# 48-17V_Buck_Converter.net
KiCad netlist of a schematic drawn in Altium Designer
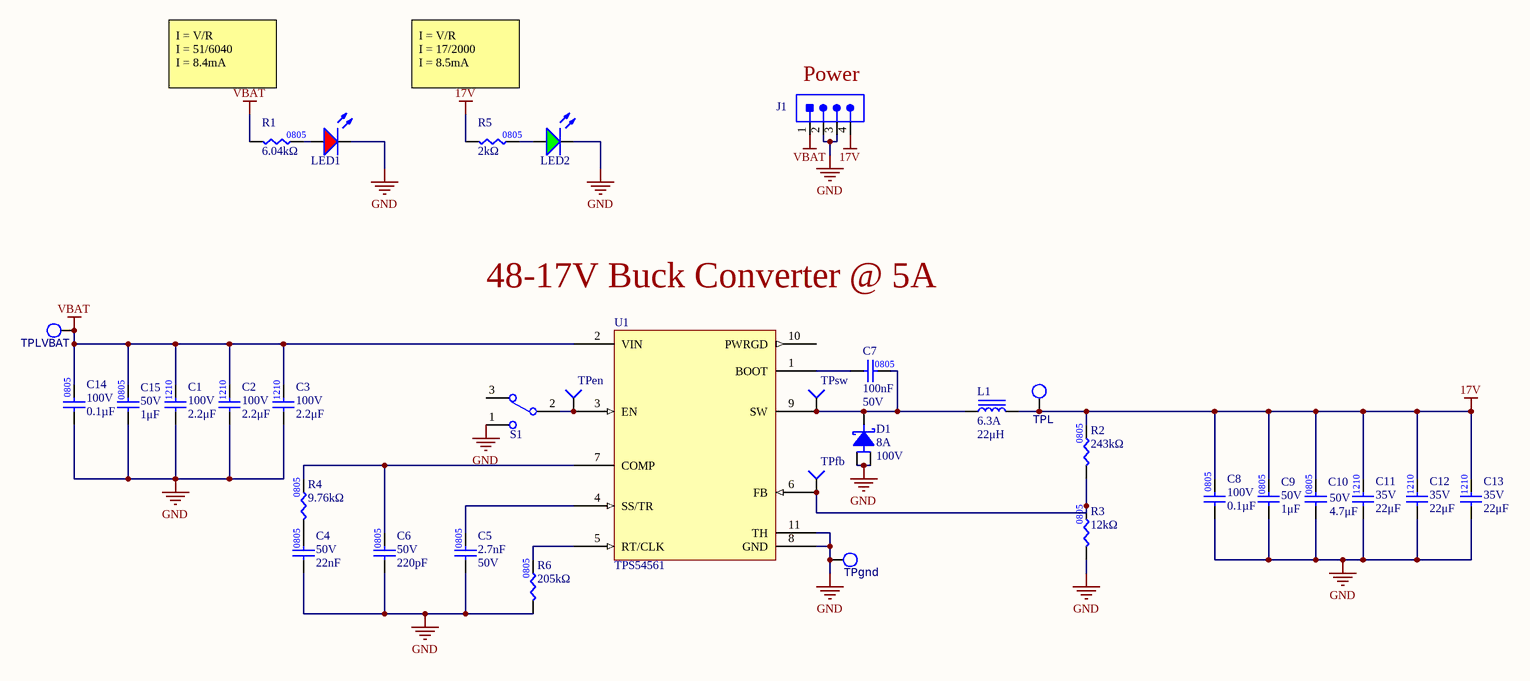
[diagram p0: 48-17V Buck Converter.SchDoc]

(export (version "E")
  (design (tool "Eeschema 10.0.6"))
  (components
    (comp (ref "C1")
      (value "2.2μF")
      (footprint "CAPC3225X270N")
      (description "CAP CER 2.2UF 100V X7R 1210")
      (fields (field (name "VOLTAGE RATING") "100V") (field (name "Comment") "CAP_2.2uF_100V_1210_1"))
      (libsource (lib "UWRT_Schematic_Library_2020") (part "CAP_2.2uF_100V_1210_1"))
    )
    (comp (ref "C2")
      (value "2.2μF")
      (footprint "CAPC3225X270N")
      (description "CAP CER 2.2UF 100V X7R 1210")
      (fields (field (name "VOLTAGE RATING") "100V") (field (name "Comment") "CAP_2.2uF_100V_1210_1"))
      (libsource (lib "UWRT_Schematic_Library_2020") (part "CAP_2.2uF_100V_1210_1"))
    )
    (comp (ref "C3")
      (value "2.2μF")
      (footprint "CAPC3225X270N")
      (description "CAP CER 2.2UF 100V X7R 1210")
      (fields (field (name "VOLTAGE RATING") "100V") (field (name "Comment") "CAP_2.2uF_100V_1210_1"))
      (libsource (lib "UWRT_Schematic_Library_2020") (part "CAP_2.2uF_100V_1210_1"))
    )
    (comp (ref "C4")
      (value "22nF")
      (footprint "CAP2012")
      (description "CAP CER 22nF 50V 0805")
      (fields (field (name "VOLTAGE RATING") "50V") (field (name "Comment") "CAP_22nF_50V_0805 +/- 1%"))
      (libsource (lib "UWRT_Schematic_Library_2020") (part "CAP_22nF_50V_0805 +/- 1%"))
    )
    (comp (ref "C5")
      (value "2.7nF")
      (footprint "CAP0805")
      (description "CAP CER 2700PF 50V C0G 0805")
      (fields (field (name "VOLTAGE RATING") "50V") (field (name "Comment") "CAP_2.7nF_50V_0805"))
      (libsource (lib "UWRT_Schematic_Library_2020") (part "CAP_2.7nF_50V_0805"))
    )
    (comp (ref "C6")
      (value "220pF")
      (footprint "CAP2012")
      (description "CAP CER 220pF 50V 0805 +/-1%")
      (fields (field (name "VOLTAGE RATING") "50V") (field (name "Comment") "CAP_220pF_50V_0805_2_1"))
      (libsource (lib "UWRT_Schematic_Library_2020") (part "CAP_220pF_50V_0805_2_1"))
    )
    (comp (ref "C7")
      (value "100nF")
      (footprint "CAP0805")
      (description "CAP CER 0.1UF 50V X7R 0805")
      (fields (field (name "VOLTAGE RATING") "50V") (field (name "Comment") "CAP_100nF_50V_0805"))
      (libsource (lib "UWRT_Schematic_Library_2020") (part "CAP_100nF_50V_0805"))
    )
    (comp (ref "C8")
      (value "0.1µF")
      (footprint "CAP0805")
      (description "CAP CER 0.1UF 100V X7R 0805")
      (fields (field (name "VOLTAGE RATING") "100V") (field (name "Comment") "CAP_0.1uF_100V_0805"))
      (libsource (lib "UWRT_Schematic_Library_2020") (part "CAP_0.1uF_100V_0805"))
    )
    (comp (ref "C9")
      (value "1μF")
      (footprint "CAP2012")
      (description "CAP CER 1UF 50V X7R 0805")
      (fields
        (field (name "LCSC PART #") "C28323")
        (field (name "VOLTAGE RATING") "50V")
        (field (name "Comment") "CAP_1uF_50V_0805")
      )
      (libsource (lib "UWRT_Schematic_Library_2020") (part "CAP_1uF_50V_0805"))
    )
    (comp (ref "C10")
      (value "4.7μF")
      (footprint "CAP0805")
      (description "CAP CER 4.7UF 50V X5R 0805")
      (fields
        (field (name "LCSC PART #") "C1779")
        (field (name "VOLTAGE RATING") "50V")
        (field (name "Comment") "CAP_4.7uF_50V_0805")
      )
      (libsource (lib "UWRT_Schematic_Library_2020") (part "CAP_4.7uF_50V_0805"))
    )
    (comp (ref "C11")
      (value "22μF")
      (footprint "CAP1210")
      (description "CAP CER 22UF 35V X5R 1210")
      (fields (field (name "VOLTAGE RATING") "35V") (field (name "Comment") "CAP_22uF_100V_1210"))
      (libsource (lib "UWRT_Schematic_Library_2020") (part "CAP_22uF_100V_1210"))
    )
    (comp (ref "C12")
      (value "22μF")
      (footprint "CAP1210")
      (description "CAP CER 22UF 35V X5R 1210")
      (fields (field (name "VOLTAGE RATING") "35V") (field (name "Comment") "CAP_22uF_100V_1210"))
      (libsource (lib "UWRT_Schematic_Library_2020") (part "CAP_22uF_100V_1210"))
    )
    (comp (ref "C13")
      (value "22μF")
      (footprint "CAP1210")
      (description "CAP CER 22UF 35V X5R 1210")
      (fields (field (name "VOLTAGE RATING") "35V") (field (name "Comment") "CAP_22uF_100V_1210"))
      (libsource (lib "UWRT_Schematic_Library_2020") (part "CAP_22uF_100V_1210"))
    )
    (comp (ref "C14")
      (value "0.1µF")
      (footprint "CAP0805")
      (description "CAP CER 0.1UF 100V X7R 0805")
      (fields (field (name "VOLTAGE RATING") "100V") (field (name "Comment") "CAP_0.1uF_100V_0805"))
      (libsource (lib "UWRT_Schematic_Library_2020") (part "CAP_0.1uF_100V_0805"))
    )
    (comp (ref "C15")
      (value "1μF")
      (footprint "CAP2012")
      (description "CAP CER 1UF 50V X7R 0805")
      (fields
        (field (name "LCSC PART #") "C28323")
        (field (name "VOLTAGE RATING") "50V")
        (field (name "Comment") "CAP_1uF_50V_0805")
      )
      (libsource (lib "UWRT_Schematic_Library_2020") (part "CAP_1uF_50V_0805"))
    )
    (comp (ref "D1")
      (value "8A")
      (footprint "TO-277")
      (description "Diode 100 V 8A Surface Mount TO-277")
      (fields (field (name "VR (MAX)") "100V"))
      (libsource (lib "UWRT_Schematic_Library_2020") (part "DIO_SCHOTTKY_100V_8A"))
    )
    (comp (ref "J1")
      (value "CON_2POS_SCREW_TERM")
      (footprint "MPT-04-01-01-L-RA-SD")
      (description "CONN HDR 4POS 5MM R/A SLDR")
      (libsource (lib "UWRT_Schematic_Library_2020") (part "CON_4POS_POWERBLADE_MALE"))
    )
    (comp (ref "L1")
      (value "IND_22uH_6.3A")
      (footprint "UWRT_Footprint_Library_2020:IND_22uH_6.3A")
      (description "FIXED IND 22UH 6.3A 25.7MOHM SMD")
      (fields (field (name "CURRENT RATING") "6.3A") (field (name "INDUCTANCE") "22μH"))
      (libsource (lib "UWRT_Schematic_Library_2020") (part "IND_22uH_6.3A"))
    )
    (comp (ref "LED1")
      (value "LED_RED")
      (footprint "LED_0805_RED")
      (description "LED RED DIFFUSED 0805 SMD")
      (libsource (lib "UWRT_Schematic_Library_2020") (part "LED_RED"))
    )
    (comp (ref "LED2")
      (value "LED_GREEN")
      (footprint "LED_0805_GREEN")
      (description "LED GREEN DIFFUSED 0805 SMD")
      (libsource (lib "UWRT_Schematic_Library_2020") (part "LED_GREEN"))
    )
    (comp (ref "R1")
      (value "6.04kΩ")
      (footprint "RES0805")
      (description "RES 6.04K OHM 1% 1/8W 0805")
      (fields (field (name "Comment") "RES_6.04kΩ_0805_1%"))
      (libsource (lib "UWRT_Schematic_Library_2020") (part "RES_6.04kΩ_0805_1%"))
    )
    (comp (ref "R2")
      (value "243kΩ")
      (footprint "RES0805")
      (description "RES 243K OHM 1% 1/8W 0805")
      (fields (field (name "Comment") "RES_243kΩ_0805_1%_1"))
      (libsource (lib "UWRT_Schematic_Library_2020") (part "RES_243kΩ_0805_1%_1"))
    )
    (comp (ref "R3")
      (value "12kΩ")
      (footprint "RES0805")
      (description "RES 12K OHM 1% 1/8W 0805")
      (fields (field (name "Comment") "RES_12kΩ_0805_1%"))
      (libsource (lib "UWRT_Schematic_Library_2020") (part "RES_12kΩ_0805_1%"))
    )
    (comp (ref "R4")
      (value "9.76kΩ")
      (footprint "RES0805")
      (description "RES 9.76K OHM 1% 1/8W 0805")
      (fields (field (name "Comment") "RES_9.76kΩ_0805_1%"))
      (libsource (lib "UWRT_Schematic_Library_2020") (part "RES_9.76kΩ_0805_1%"))
    )
    (comp (ref "R5")
      (value "2kΩ")
      (footprint "RES0805")
      (description "RES 2K OHM 1% 1/8W 0805")
      (fields (field (name "TOLERANCE") "1%") (field (name "Comment") "RES_2KΩ_0805_1%"))
      (libsource (lib "UWRT_Schematic_Library_2020") (part "RES_2KΩ_0805_1%"))
    )
    (comp (ref "R6")
      (value "205kΩ")
      (footprint "RES0805")
      (description "RES 205K OHM 1% 1/8W 0805")
      (fields (field (name "Comment") "RES_205kΩ_0805_1%"))
      (libsource (lib "UWRT_Schematic_Library_2020") (part "RES_205kΩ_0805_1%"))
    )
    (comp (ref "S1")
      (value "SW_SLIDE_TOGGLE")
      (footprint "UWRT_Footprint_Library_2020:SW_SLIDE_TOGGLE")
      (description "SWITCH SLIDE SPDT 200MA 30V")
      (libsource (lib "UWRT_Schematic_Library_2020") (part "SW_SLIDE_TOGGLE"))
    )
    (comp (ref "TPen")
      (value "TESTPOINT_1MM_CIRCLE")
      (footprint "TESTPOINT_CIRCLE_1MM")
      (description "TESTPOINT 1MM CIRCLE")
      (libsource (lib "UWRT_Schematic_Library_2020") (part "TESTPOINT_1MM_CIRCLE"))
    )
    (comp (ref "TPfb")
      (value "TESTPOINT_1MM_CIRCLE")
      (footprint "TESTPOINT_CIRCLE_1MM")
      (description "TESTPOINT 1MM CIRCLE")
      (libsource (lib "UWRT_Schematic_Library_2020") (part "TESTPOINT_1MM_CIRCLE"))
    )
    (comp (ref "TPgnd")
      (value "TESTPOINT_LOOP")
      (footprint "TESTPOINT_LOOP")
      (description "TESTPOINT THRUHOLE")
      (libsource (lib "UWRT_Schematic_Library_2020") (part "TESTPOINT_LOOP"))
    )
    (comp (ref "TPL")
      (value "TESTPOINT_LOOP")
      (footprint "TESTPOINT_LOOP")
      (description "TESTPOINT THRUHOLE")
      (libsource (lib "UWRT_Schematic_Library_2020") (part "TESTPOINT_LOOP"))
    )
    (comp (ref "TPLVBAT")
      (value "TESTPOINT_LOOP")
      (footprint "TESTPOINT_LOOP")
      (description "TESTPOINT THRUHOLE")
      (libsource (lib "UWRT_Schematic_Library_2020") (part "TESTPOINT_LOOP"))
    )
    (comp (ref "TPsw")
      (value "TESTPOINT_1MM_CIRCLE")
      (footprint "TESTPOINT_CIRCLE_1MM")
      (description "TESTPOINT 1MM CIRCLE")
      (libsource (lib "UWRT_Schematic_Library_2020") (part "TESTPOINT_1MM_CIRCLE"))
    )
    (comp (ref "U1")
      (value "TPS54561")
      (footprint "BUCK_TPS54561DPRR")
      (description "Buck Switching Regulator IC Positive Adjustable 0.8V 1 Output 5A 10-WDFN Exposed Pad")
      (libsource (lib "UWRT_Schematic_Library_2020") (part "TPS54561"))
    )
  )
  (nets
    (net (code "1") (name "17V") (class "Default")
      (node (ref "C10") (pin "2") (pinfunction "2_2") (pintype "passive"))
      (node (ref "C11") (pin "2") (pinfunction "2_2") (pintype "passive"))
      (node (ref "C12") (pin "2") (pinfunction "2_2") (pintype "passive"))
      (node (ref "C13") (pin "2") (pinfunction "2_2") (pintype "passive"))
      (node (ref "C8") (pin "2") (pinfunction "2_2") (pintype "passive"))
      (node (ref "C9") (pin "2") (pinfunction "2_2") (pintype "passive"))
      (node (ref "J1") (pin "4") (pinfunction "2_4") (pintype "passive"))
      (node (ref "L1") (pin "2") (pinfunction "2_2") (pintype "passive"))
      (node (ref "R2") (pin "2") (pinfunction "2_2") (pintype "passive"))
      (node (ref "R5") (pin "1") (pinfunction "1_1") (pintype "passive"))
      (node (ref "TPL") (pin "1") (pintype "passive"))
    )
    (net (code "2") (name "GND") (class "Default")
      (node (ref "C1") (pin "1") (pinfunction "1_1") (pintype "passive"))
      (node (ref "C10") (pin "1") (pinfunction "1_1") (pintype "passive"))
      (node (ref "C11") (pin "1") (pinfunction "1_1") (pintype "passive"))
      (node (ref "C12") (pin "1") (pinfunction "1_1") (pintype "passive"))
      (node (ref "C13") (pin "1") (pinfunction "1_1") (pintype "passive"))
      (node (ref "C14") (pin "1") (pinfunction "1_1") (pintype "passive"))
      (node (ref "C15") (pin "1") (pinfunction "1_1") (pintype "passive"))
      (node (ref "C2") (pin "1") (pinfunction "1_1") (pintype "passive"))
      (node (ref "C3") (pin "1") (pinfunction "1_1") (pintype "passive"))
      (node (ref "C4") (pin "1") (pinfunction "1_1") (pintype "passive"))
      (node (ref "C5") (pin "1") (pinfunction "1_1") (pintype "passive"))
      (node (ref "C6") (pin "1") (pinfunction "1_1") (pintype "passive"))
      (node (ref "C8") (pin "1") (pinfunction "1_1") (pintype "passive"))
      (node (ref "C9") (pin "1") (pinfunction "1_1") (pintype "passive"))
      (node (ref "D1") (pin "1") (pinfunction "Anode_1") (pintype "passive"))
      (node (ref "D1") (pin "3") (pintype "passive"))
      (node (ref "J1") (pin "2") (pinfunction "2_2") (pintype "passive"))
      (node (ref "J1") (pin "3") (pinfunction "1_3") (pintype "passive"))
      (node (ref "LED1") (pin "2") (pinfunction "K_2") (pintype "passive"))
      (node (ref "LED2") (pin "2") (pinfunction "K_2") (pintype "passive"))
      (node (ref "R3") (pin "1") (pinfunction "1_1") (pintype "passive"))
      (node (ref "R6") (pin "1") (pinfunction "1_1") (pintype "passive"))
      (node (ref "S1") (pin "1") (pinfunction "1_1") (pintype "passive"))
      (node (ref "TPgnd") (pin "1") (pintype "passive"))
      (node (ref "U1") (pin "11") (pinfunction "TH_11") (pintype "power_in"))
      (node (ref "U1") (pin "8") (pinfunction "GND_8") (pintype "power_in"))
    )
    (net (code "3") (name "Net-(C4-Pad2)") (class "Default")
      (node (ref "C4") (pin "2") (pinfunction "2_2") (pintype "passive"))
      (node (ref "R4") (pin "1") (pinfunction "1_1") (pintype "passive"))
    )
    (net (code "4") (name "Net-(D1-Cathode)") (class "Default")
      (node (ref "C7") (pin "2") (pinfunction "2_2") (pintype "passive"))
      (node (ref "D1") (pin "2") (pinfunction "Cathode_2") (pintype "passive"))
      (node (ref "L1") (pin "1") (pinfunction "1_1") (pintype "passive"))
      (node (ref "TPsw") (pin "1") (pinfunction "=value_1") (pintype "passive"))
      (node (ref "U1") (pin "9") (pinfunction "SW_9") (pintype "power_in"))
    )
    (net (code "5") (name "Net-(LED1-A)") (class "Default")
      (node (ref "LED1") (pin "1") (pinfunction "A_1") (pintype "passive"))
      (node (ref "R1") (pin "2") (pinfunction "2_2") (pintype "passive"))
    )
    (net (code "6") (name "Net-(LED2-A)") (class "Default")
      (node (ref "LED2") (pin "1") (pinfunction "A_1") (pintype "passive"))
      (node (ref "R5") (pin "2") (pinfunction "2_2") (pintype "passive"))
    )
    (net (code "7") (name "Net-(TPen-=value)") (class "Default")
      (node (ref "S1") (pin "2") (pinfunction "2_2") (pintype "passive"))
      (node (ref "TPen") (pin "1") (pinfunction "=value_1") (pintype "passive"))
      (node (ref "U1") (pin "3") (pinfunction "EN_3") (pintype "input"))
    )
    (net (code "8") (name "Net-(TPfb-=value)") (class "Default")
      (node (ref "R2") (pin "1") (pinfunction "1_1") (pintype "passive"))
      (node (ref "R3") (pin "2") (pinfunction "2_2") (pintype "passive"))
      (node (ref "TPfb") (pin "1") (pinfunction "=value_1") (pintype "passive"))
      (node (ref "U1") (pin "6") (pinfunction "FB_6") (pintype "input"))
    )
    (net (code "9") (name "Net-(U1-BOOT)") (class "Default")
      (node (ref "C7") (pin "1") (pinfunction "1_1") (pintype "passive"))
      (node (ref "U1") (pin "1") (pinfunction "BOOT_1") (pintype "power_in"))
    )
    (net (code "10") (name "Net-(U1-COMP)") (class "Default")
      (node (ref "C6") (pin "2") (pinfunction "2_2") (pintype "passive"))
      (node (ref "R4") (pin "2") (pinfunction "2_2") (pintype "passive"))
      (node (ref "U1") (pin "7") (pinfunction "COMP_7") (pintype "power_in"))
    )
    (net (code "11") (name "Net-(U1-RT{slash}CLK)") (class "Default")
      (node (ref "R6") (pin "2") (pinfunction "2_2") (pintype "passive"))
      (node (ref "U1") (pin "5") (pinfunction "RT/CLK_5") (pintype "input"))
    )
    (net (code "12") (name "Net-(U1-SS{slash}TR)") (class "Default")
      (node (ref "C5") (pin "2") (pinfunction "2_2") (pintype "passive"))
      (node (ref "U1") (pin "4") (pinfunction "SS/TR_4") (pintype "input"))
    )
    (net (code "13") (name "VBAT") (class "Default")
      (node (ref "C1") (pin "2") (pinfunction "2_2") (pintype "passive"))
      (node (ref "C14") (pin "2") (pinfunction "2_2") (pintype "passive"))
      (node (ref "C15") (pin "2") (pinfunction "2_2") (pintype "passive"))
      (node (ref "C2") (pin "2") (pinfunction "2_2") (pintype "passive"))
      (node (ref "C3") (pin "2") (pinfunction "2_2") (pintype "passive"))
      (node (ref "J1") (pin "1") (pinfunction "1_1") (pintype "passive"))
      (node (ref "R1") (pin "1") (pinfunction "1_1") (pintype "passive"))
      (node (ref "TPLVBAT") (pin "1") (pintype "passive"))
      (node (ref "U1") (pin "2") (pinfunction "VIN_2") (pintype "power_in"))
    )
    (net (code "14") (name "unconnected-(S1-Pad3)") (class "Default")
      (node (ref "S1") (pin "3") (pinfunction "3_3") (pintype "passive"))
    )
    (net (code "15") (name "unconnected-(U1-PWRGD-Pad10)") (class "Default")
      (node (ref "U1") (pin "10") (pinfunction "PWRGD_10") (pintype "output"))
    )
  )
)
